# led_master.net
KiCad netlist of a schematic drawn in EAGLE
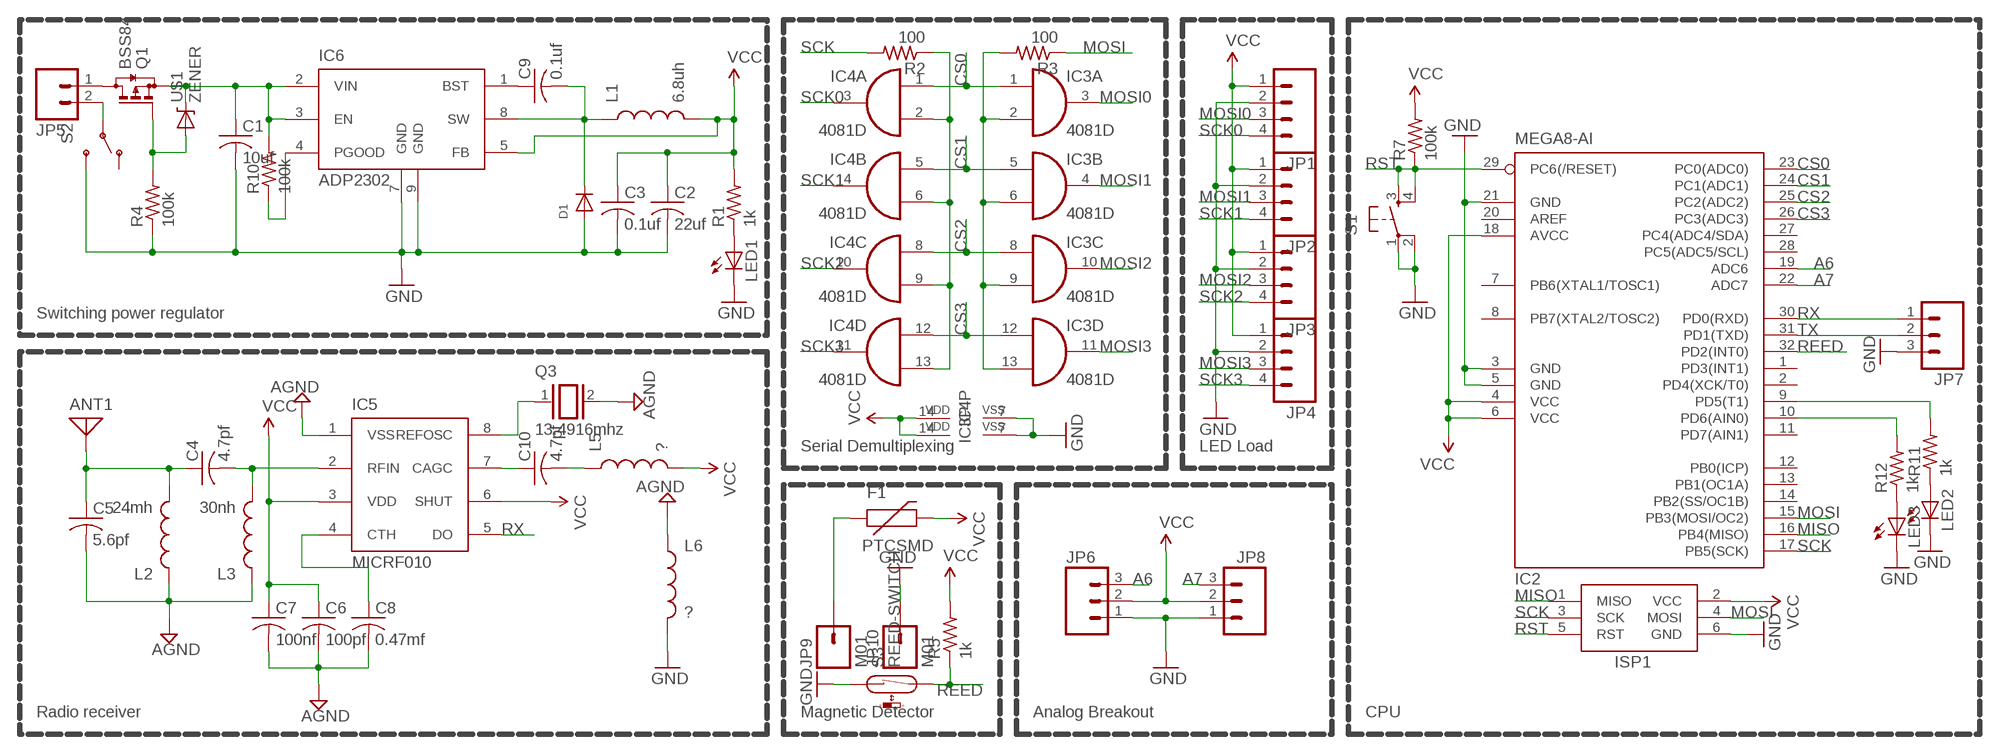
[diagram p0: schematic, sheet 1]

(export (version "E")
  (design (tool "Eeschema 10.0.6"))
  (components
    (comp (ref "ANT1")
      (value "ANTENNA")
      (footprint "eagle-import:PAD-01")
      (libsource (lib "eagle-import") (part "ANTENNA"))
    )
    (comp (ref "C1")
      (value "10uf")
      (footprint "eagle-import:C1206")
      (libsource (lib "eagle-import") (part "C-USC1206"))
    )
    (comp (ref "C2")
      (value "22uf")
      (footprint "eagle-import:C1206")
      (libsource (lib "eagle-import") (part "C-USC1206"))
    )
    (comp (ref "C3")
      (value "0.1uf")
      (footprint "eagle-import:C1206")
      (libsource (lib "eagle-import") (part "C-USC1206"))
    )
    (comp (ref "C4")
      (value "4.7pf")
      (footprint "eagle-import:C1206")
      (libsource (lib "eagle-import") (part "C-USC1206"))
    )
    (comp (ref "C5")
      (value "5.6pf")
      (footprint "eagle-import:C1206")
      (libsource (lib "eagle-import") (part "C-USC1206"))
    )
    (comp (ref "C6")
      (value "100pf")
      (footprint "eagle-import:C1206")
      (libsource (lib "eagle-import") (part "C-USC1206"))
    )
    (comp (ref "C7")
      (value "100nf")
      (footprint "eagle-import:C1206")
      (libsource (lib "eagle-import") (part "C-USC1206"))
    )
    (comp (ref "C8")
      (value "0.47mf")
      (footprint "eagle-import:C1206")
      (libsource (lib "eagle-import") (part "C-USC1206"))
    )
    (comp (ref "C9")
      (value "0.1uf")
      (footprint "eagle-import:C1206")
      (libsource (lib "eagle-import") (part "C-USC1206"))
    )
    (comp (ref "C10")
      (value "4.7pf")
      (footprint "eagle-import:C1206")
      (libsource (lib "eagle-import") (part "C-USC1206"))
    )
    (comp (ref "D1")
      (value "DIODESOD-123")
      (footprint "eagle-import:SOD-123")
      (libsource (lib "eagle-import") (part "DIODESOD-123"))
    )
    (comp (ref "F1")
      (value "PTCSMD")
      (footprint "eagle-import:PTC-1206")
      (libsource (lib "eagle-import") (part "PTCSMD"))
    )
    (comp (ref "IC2")
      (value "MEGA8-AI")
      (footprint "eagle-import:TQFP32-08")
      (fields (field (name "MPN") "ATMEGA8-16AU"))
      (libsource (lib "eagle-import") (part "MEGA8-AI"))
    )
    (comp (ref "IC3")
      (value "4081D")
      (footprint "eagle-import:SO14")
      (libsource (lib "eagle-import") (part "4081D"))
    )
    (comp (ref "IC4")
      (value "4081D")
      (footprint "eagle-import:SO14")
      (libsource (lib "eagle-import") (part "4081D"))
    )
    (comp (ref "IC5")
      (value "MICRF010")
      (footprint "eagle-import:SOIC8")
      (libsource (lib "eagle-import") (part "MICRF010"))
    )
    (comp (ref "IC6")
      (value "ADP2302")
      (footprint "eagle-import:SOIC8-PAD")
      (libsource (lib "eagle-import") (part "ADP2302"))
    )
    (comp (ref "ISP1")
      (value "AVRISP-6")
      (footprint "eagle-import:AVRISP")
      (libsource (lib "eagle-import") (part "AVRISP-6"))
    )
    (comp (ref "JP1")
      (value "M04LONGPADS")
      (footprint "eagle-import:1X04_LONGPADS")
      (libsource (lib "eagle-import") (part "M04LONGPADS"))
    )
    (comp (ref "JP2")
      (value "M04LONGPADS")
      (footprint "eagle-import:1X04_LONGPADS")
      (libsource (lib "eagle-import") (part "M04LONGPADS"))
    )
    (comp (ref "JP3")
      (value "M04LONGPADS")
      (footprint "eagle-import:1X04_LONGPADS")
      (libsource (lib "eagle-import") (part "M04LONGPADS"))
    )
    (comp (ref "JP4")
      (value "M04LONGPADS")
      (footprint "eagle-import:1X04_LONGPADS")
      (libsource (lib "eagle-import") (part "M04LONGPADS"))
    )
    (comp (ref "JP5")
      (value "M02-JST-2MM-SMT")
      (footprint "eagle-import:JST-2-SMD")
      (libsource (lib "eagle-import") (part "M02-JST-2MM-SMT"))
    )
    (comp (ref "JP6")
      (value "M03PTH")
      (footprint "eagle-import:1X03")
      (libsource (lib "eagle-import") (part "M03PTH"))
    )
    (comp (ref "JP7")
      (value "M03PTH")
      (footprint "eagle-import:1X03")
      (libsource (lib "eagle-import") (part "M03PTH"))
    )
    (comp (ref "JP8")
      (value "M03PTH")
      (footprint "eagle-import:1X03")
      (libsource (lib "eagle-import") (part "M03PTH"))
    )
    (comp (ref "JP9")
      (value "M01")
      (footprint "eagle-import:SMTSO-256-ET")
      (libsource (lib "eagle-import") (part "M01-SMTSO-256-ET"))
    )
    (comp (ref "JP10")
      (value "M01")
      (footprint "eagle-import:SMTSO-256-ET")
      (libsource (lib "eagle-import") (part "M01-SMTSO-256-ET"))
    )
    (comp (ref "L1")
      (value "6.8uh")
      (footprint "eagle-import:1210")
      (libsource (lib "eagle-import") (part "INDUCTOR1210"))
    )
    (comp (ref "L2")
      (value "24mh")
      (footprint "eagle-import:1210")
      (libsource (lib "eagle-import") (part "INDUCTOR1210"))
    )
    (comp (ref "L3")
      (value "30nh")
      (footprint "eagle-import:1210")
      (libsource (lib "eagle-import") (part "INDUCTOR1210"))
    )
    (comp (ref "L5")
      (value "?")
      (footprint "eagle-import:1210")
      (libsource (lib "eagle-import") (part "INDUCTOR1210"))
    )
    (comp (ref "L6")
      (value "?")
      (footprint "eagle-import:1210")
      (libsource (lib "eagle-import") (part "INDUCTOR1210"))
    )
    (comp (ref "LED1")
      (value "LEDSMT1206")
      (footprint "eagle-import:1206")
      (libsource (lib "eagle-import") (part "LEDSMT1206"))
    )
    (comp (ref "LED2")
      (value "LEDSMT1206")
      (footprint "eagle-import:1206")
      (libsource (lib "eagle-import") (part "LEDSMT1206"))
    )
    (comp (ref "LED3")
      (value "LEDSMT1206")
      (footprint "eagle-import:1206")
      (libsource (lib "eagle-import") (part "LEDSMT1206"))
    )
    (comp (ref "Q1")
      (value "BSS84")
      (footprint "eagle-import:SOT23")
      (libsource (lib "eagle-import") (part "BSS84"))
    )
    (comp (ref "Q3")
      (value "13.4916mhz")
      (footprint "eagle-import:QS")
      (libsource (lib "eagle-import") (part "XTAL/S"))
    )
    (comp (ref "R1")
      (value "1k")
      (footprint "eagle-import:R1206")
      (libsource (lib "eagle-import") (part "R-US_R1206"))
    )
    (comp (ref "R2")
      (value "100")
      (footprint "eagle-import:R1206")
      (libsource (lib "eagle-import") (part "R-US_R1206"))
    )
    (comp (ref "R3")
      (value "100")
      (footprint "eagle-import:R1206")
      (libsource (lib "eagle-import") (part "R-US_R1206"))
    )
    (comp (ref "R4")
      (value "100k")
      (footprint "eagle-import:R1206")
      (libsource (lib "eagle-import") (part "R-US_R1206"))
    )
    (comp (ref "R5")
      (value "1k")
      (footprint "eagle-import:R1206")
      (libsource (lib "eagle-import") (part "R-US_R1206"))
    )
    (comp (ref "R7")
      (value "100k")
      (footprint "eagle-import:R1206")
      (libsource (lib "eagle-import") (part "R-US_R1206"))
    )
    (comp (ref "R10")
      (value "100k")
      (footprint "eagle-import:R1206")
      (libsource (lib "eagle-import") (part "R-US_R1206"))
    )
    (comp (ref "R11")
      (value "1k")
      (footprint "eagle-import:R1206")
      (libsource (lib "eagle-import") (part "R-US_R1206"))
    )
    (comp (ref "R12")
      (value "1k")
      (footprint "eagle-import:R1206")
      (libsource (lib "eagle-import") (part "R-US_R1206"))
    )
    (comp (ref "S1")
      (value "TAC_SWITCHSMD")
      (footprint "eagle-import:TACTILE_SWITCH_SMD")
      (libsource (lib "eagle-import") (part "TAC_SWITCHSMD"))
    )
    (comp (ref "S2")
      (value "SWITCH-SPSTSMD2")
      (footprint "eagle-import:SWITCH-SPDT-SMD")
      (libsource (lib "eagle-import") (part "SWITCH-SPSTSMD2"))
    )
    (comp (ref "S3")
      (value "REED-SWITCH")
      (footprint "eagle-import:CT10-G1")
      (fields (field (name "MF") "COTO TECHNOLOGY") (field (name "MPN") "CT10-1530-G1"))
      (libsource (lib "eagle-import") (part "REED-SWITCH-CT10-1530-G1"))
    )
    (comp (ref "U$1")
      (value "ZENER")
      (footprint "eagle-import:SOD-323")
      (libsource (lib "eagle-import") (part "DIODE-ZENER-BZT52"))
    )
  )
  (nets
    (net (code "1") (name "/A6") (class "Default")
      (node (ref "IC2") (pin "19") (pinfunction "ADC6_19") (pintype "bidirectional"))
      (node (ref "JP6") (pin "3") (pinfunction "3_3") (pintype "passive"))
    )
    (net (code "2") (name "/A7") (class "Default")
      (node (ref "IC2") (pin "22") (pinfunction "ADC7_22") (pintype "bidirectional"))
      (node (ref "JP8") (pin "3") (pinfunction "3_3") (pintype "passive"))
    )
    (net (code "3") (name "/CS0") (class "Default")
      (node (ref "IC2") (pin "23") (pinfunction "PC0(ADC0)_23") (pintype "bidirectional"))
      (node (ref "IC3") (pin "1") (pinfunction "I0_1") (pintype "input"))
      (node (ref "IC4") (pin "1") (pinfunction "I0_1") (pintype "input"))
    )
    (net (code "4") (name "/CS1") (class "Default")
      (node (ref "IC2") (pin "24") (pinfunction "PC1(ADC1)_24") (pintype "bidirectional"))
      (node (ref "IC3") (pin "5") (pinfunction "I0_5") (pintype "input"))
      (node (ref "IC4") (pin "5") (pinfunction "I0_5") (pintype "input"))
    )
    (net (code "5") (name "/CS2") (class "Default")
      (node (ref "IC2") (pin "25") (pinfunction "PC2(ADC2)_25") (pintype "bidirectional"))
      (node (ref "IC3") (pin "8") (pinfunction "I0_8") (pintype "input"))
      (node (ref "IC4") (pin "8") (pinfunction "I0_8") (pintype "input"))
    )
    (net (code "6") (name "/CS3") (class "Default")
      (node (ref "IC2") (pin "26") (pinfunction "PC3(ADC3)_26") (pintype "bidirectional"))
      (node (ref "IC3") (pin "12") (pinfunction "I0_12") (pintype "input"))
      (node (ref "IC4") (pin "12") (pinfunction "I0_12") (pintype "input"))
    )
    (net (code "7") (name "/MISO") (class "Default")
      (node (ref "IC2") (pin "16") (pinfunction "PB4(MISO)_16") (pintype "bidirectional"))
      (node (ref "ISP1") (pin "1") (pinfunction "MISO_1") (pintype "input"))
    )
    (net (code "8") (name "/MOSI") (class "Default")
      (node (ref "IC2") (pin "15") (pinfunction "PB3(MOSI/OC2)_15") (pintype "bidirectional"))
      (node (ref "ISP1") (pin "4") (pinfunction "MOSI_4") (pintype "output"))
      (node (ref "R3") (pin "1") (pinfunction "1_1") (pintype "passive"))
    )
    (net (code "9") (name "/MOSI0") (class "Default")
      (node (ref "IC3") (pin "3") (pinfunction "O_3") (pintype "output"))
      (node (ref "JP1") (pin "3") (pinfunction "3_3") (pintype "passive"))
    )
    (net (code "10") (name "/MOSI1") (class "Default")
      (node (ref "IC3") (pin "4") (pinfunction "O_4") (pintype "output"))
      (node (ref "JP2") (pin "3") (pinfunction "3_3") (pintype "passive"))
    )
    (net (code "11") (name "/MOSI2") (class "Default")
      (node (ref "IC3") (pin "10") (pinfunction "O_10") (pintype "output"))
      (node (ref "JP3") (pin "3") (pinfunction "3_3") (pintype "passive"))
    )
    (net (code "12") (name "/MOSI3") (class "Default")
      (node (ref "IC3") (pin "11") (pinfunction "O_11") (pintype "output"))
      (node (ref "JP4") (pin "3") (pinfunction "3_3") (pintype "passive"))
    )
    (net (code "13") (name "/REED") (class "Default")
      (node (ref "IC2") (pin "32") (pinfunction "PD2(INT0)_32") (pintype "bidirectional"))
      (node (ref "R5") (pin "1") (pinfunction "1_1") (pintype "passive"))
      (node (ref "S3") (pin "2") (pinfunction "2_2") (pintype "passive"))
    )
    (net (code "14") (name "/RST") (class "Default")
      (node (ref "IC2") (pin "29") (pinfunction "PC6(/RESET)_29") (pintype "bidirectional"))
      (node (ref "ISP1") (pin "5") (pinfunction "RST_5") (pintype "output"))
      (node (ref "R7") (pin "1") (pinfunction "1_1") (pintype "passive"))
      (node (ref "S1") (pin "3") (pinfunction "3_3") (pintype "passive"))
      (node (ref "S1") (pin "4") (pinfunction "4_4") (pintype "passive"))
    )
    (net (code "15") (name "/RX") (class "Default")
      (node (ref "IC2") (pin "30") (pinfunction "PD0(RXD)_30") (pintype "bidirectional"))
      (node (ref "IC5") (pin "5") (pinfunction "DO_5") (pintype "bidirectional"))
      (node (ref "JP7") (pin "1") (pinfunction "1_1") (pintype "passive"))
    )
    (net (code "16") (name "/SCK") (class "Default")
      (node (ref "IC2") (pin "17") (pinfunction "PB5(SCK)_17") (pintype "bidirectional"))
      (node (ref "ISP1") (pin "3") (pinfunction "SCK_3") (pintype "output"))
      (node (ref "R2") (pin "2") (pinfunction "2_2") (pintype "passive"))
    )
    (net (code "17") (name "/SCK0") (class "Default")
      (node (ref "IC4") (pin "3") (pinfunction "O_3") (pintype "output"))
      (node (ref "JP1") (pin "4") (pinfunction "4_4") (pintype "passive"))
    )
    (net (code "18") (name "/SCK1") (class "Default")
      (node (ref "IC4") (pin "4") (pinfunction "O_4") (pintype "output"))
      (node (ref "JP2") (pin "4") (pinfunction "4_4") (pintype "passive"))
    )
    (net (code "19") (name "/SCK2") (class "Default")
      (node (ref "IC4") (pin "10") (pinfunction "O_10") (pintype "output"))
      (node (ref "JP3") (pin "4") (pinfunction "4_4") (pintype "passive"))
    )
    (net (code "20") (name "/SCK3") (class "Default")
      (node (ref "IC4") (pin "11") (pinfunction "O_11") (pintype "output"))
      (node (ref "JP4") (pin "4") (pinfunction "4_4") (pintype "passive"))
    )
    (net (code "21") (name "/TX") (class "Default")
      (node (ref "IC2") (pin "31") (pinfunction "PD1(TXD)_31") (pintype "bidirectional"))
      (node (ref "JP7") (pin "2") (pinfunction "2_2") (pintype "passive"))
    )
    (net (code "22") (name "AGND") (class "Default")
      (node (ref "C5") (pin "2") (pinfunction "2_2") (pintype "passive"))
      (node (ref "C6") (pin "2") (pinfunction "2_2") (pintype "passive"))
      (node (ref "C7") (pin "2") (pinfunction "2_2") (pintype "passive"))
      (node (ref "C8") (pin "2") (pinfunction "2_2") (pintype "passive"))
      (node (ref "IC5") (pin "1") (pinfunction "VSS_1") (pintype "bidirectional"))
      (node (ref "L2") (pin "1") (pinfunction "1_1") (pintype "passive"))
      (node (ref "L3") (pin "1") (pinfunction "1_1") (pintype "passive"))
      (node (ref "L6") (pin "1") (pinfunction "1_1") (pintype "passive"))
      (node (ref "Q3") (pin "2") (pinfunction "2_2") (pintype "passive"))
    )
    (net (code "23") (name "GND") (class "Default")
      (node (ref "C1") (pin "2") (pinfunction "2_2") (pintype "passive"))
      (node (ref "C2") (pin "2") (pinfunction "2_2") (pintype "passive"))
      (node (ref "C3") (pin "2") (pinfunction "2_2") (pintype "passive"))
      (node (ref "D1") (pin "A") (pinfunction "A_A") (pintype "passive"))
      (node (ref "IC2") (pin "21") (pinfunction "GND_21") (pintype "power_in"))
      (node (ref "IC2") (pin "3") (pinfunction "GND_3") (pintype "power_in"))
      (node (ref "IC2") (pin "5") (pinfunction "GND_5") (pintype "power_in"))
      (node (ref "IC3") (pin "7") (pinfunction "VSS_7") (pintype "power_in"))
      (node (ref "IC4") (pin "7") (pinfunction "VSS_7") (pintype "power_in"))
      (node (ref "IC6") (pin "7") (pinfunction "GND_7") (pintype "bidirectional"))
      (node (ref "IC6") (pin "9") (pinfunction "GND_9") (pintype "bidirectional"))
      (node (ref "ISP1") (pin "6") (pinfunction "GND_6") (pintype "power_in"))
      (node (ref "JP1") (pin "2") (pinfunction "2_2") (pintype "passive"))
      (node (ref "JP10") (pin "P$1") (pinfunction "1_P$1") (pintype "passive"))
      (node (ref "JP2") (pin "2") (pinfunction "2_2") (pintype "passive"))
      (node (ref "JP3") (pin "2") (pinfunction "2_2") (pintype "passive"))
      (node (ref "JP4") (pin "2") (pinfunction "2_2") (pintype "passive"))
      (node (ref "JP6") (pin "1") (pinfunction "1_1") (pintype "passive"))
      (node (ref "JP7") (pin "3") (pinfunction "3_3") (pintype "passive"))
      (node (ref "JP8") (pin "1") (pinfunction "1_1") (pintype "passive"))
      (node (ref "L6") (pin "2") (pinfunction "2_2") (pintype "passive"))
      (node (ref "LED1") (pin "C") (pinfunction "C_C") (pintype "passive"))
      (node (ref "LED2") (pin "C") (pinfunction "C_C") (pintype "passive"))
      (node (ref "LED3") (pin "C") (pinfunction "C_C") (pintype "passive"))
      (node (ref "R4") (pin "1") (pinfunction "1_1") (pintype "passive"))
      (node (ref "S1") (pin "1") (pinfunction "1_1") (pintype "passive"))
      (node (ref "S1") (pin "2") (pinfunction "2_2") (pintype "passive"))
      (node (ref "S2") (pin "3") (pinfunction "S_3") (pintype "passive"))
      (node (ref "S3") (pin "1") (pinfunction "1_1") (pintype "passive"))
    )
    (net (code "24") (name "Net-(ANT1-Pad1)") (class "Default")
      (node (ref "ANT1") (pin "1") (pinfunction "1_1") (pintype "output"))
      (node (ref "C4") (pin "1") (pinfunction "1_1") (pintype "passive"))
      (node (ref "C5") (pin "1") (pinfunction "1_1") (pintype "passive"))
      (node (ref "L2") (pin "2") (pinfunction "2_2") (pintype "passive"))
    )
    (net (code "25") (name "Net-(C10-Pad2)") (class "Default")
      (node (ref "C10") (pin "2") (pinfunction "2_2") (pintype "passive"))
      (node (ref "L5") (pin "1") (pinfunction "1_1") (pintype "passive"))
    )
    (net (code "26") (name "Net-(IC2-PD5(T1))") (class "Default")
      (node (ref "IC2") (pin "9") (pinfunction "PD5(T1)_9") (pintype "bidirectional"))
      (node (ref "R11") (pin "2") (pinfunction "2_2") (pintype "passive"))
    )
    (net (code "27") (name "Net-(IC2-PD6(AIN0))") (class "Default")
      (node (ref "IC2") (pin "10") (pinfunction "PD6(AIN0)_10") (pintype "bidirectional"))
      (node (ref "R12") (pin "2") (pinfunction "2_2") (pintype "passive"))
    )
    (net (code "28") (name "Net-(IC3A-I1)") (class "Default")
      (node (ref "IC3") (pin "13") (pinfunction "I1_13") (pintype "input"))
      (node (ref "IC3") (pin "2") (pinfunction "I1_2") (pintype "input"))
      (node (ref "IC3") (pin "6") (pinfunction "I1_6") (pintype "input"))
      (node (ref "IC3") (pin "9") (pinfunction "I1_9") (pintype "input"))
      (node (ref "R3") (pin "2") (pinfunction "2_2") (pintype "passive"))
    )
    (net (code "29") (name "Net-(IC4A-I1)") (class "Default")
      (node (ref "IC4") (pin "13") (pinfunction "I1_13") (pintype "input"))
      (node (ref "IC4") (pin "2") (pinfunction "I1_2") (pintype "input"))
      (node (ref "IC4") (pin "6") (pinfunction "I1_6") (pintype "input"))
      (node (ref "IC4") (pin "9") (pinfunction "I1_9") (pintype "input"))
      (node (ref "R2") (pin "1") (pinfunction "1_1") (pintype "passive"))
    )
    (net (code "30") (name "Net-(IC5-CAGC)") (class "Default")
      (node (ref "C10") (pin "1") (pinfunction "1_1") (pintype "passive"))
      (node (ref "IC5") (pin "7") (pinfunction "CAGC_7") (pintype "bidirectional"))
    )
    (net (code "31") (name "Net-(IC5-CTH)") (class "Default")
      (node (ref "C8") (pin "1") (pinfunction "1_1") (pintype "passive"))
      (node (ref "IC5") (pin "4") (pinfunction "CTH_4") (pintype "bidirectional"))
    )
    (net (code "32") (name "Net-(IC5-REFOSC)") (class "Default")
      (node (ref "IC5") (pin "8") (pinfunction "REFOSC_8") (pintype "bidirectional"))
      (node (ref "Q3") (pin "1") (pinfunction "1_1") (pintype "passive"))
    )
    (net (code "33") (name "Net-(IC5-RFIN)") (class "Default")
      (node (ref "C4") (pin "2") (pinfunction "2_2") (pintype "passive"))
      (node (ref "IC5") (pin "2") (pinfunction "RFIN_2") (pintype "bidirectional"))
      (node (ref "L3") (pin "2") (pinfunction "2_2") (pintype "passive"))
    )
    (net (code "34") (name "Net-(IC6-BST)") (class "Default")
      (node (ref "C9") (pin "1") (pinfunction "1_1") (pintype "passive"))
      (node (ref "IC6") (pin "1") (pinfunction "BST_1") (pintype "bidirectional"))
    )
    (net (code "35") (name "Net-(IC6-EN)") (class "Default")
      (node (ref "C1") (pin "1") (pinfunction "1_1") (pintype "passive"))
      (node (ref "IC6") (pin "2") (pinfunction "VIN_2") (pintype "bidirectional"))
      (node (ref "IC6") (pin "3") (pinfunction "EN_3") (pintype "bidirectional"))
      (node (ref "Q1") (pin "2") (pinfunction "S_2") (pintype "passive"))
      (node (ref "R10") (pin "2") (pinfunction "2_2") (pintype "passive"))
      (node (ref "U$1") (pin "1") (pinfunction "C_1") (pintype "passive"))
    )
    (net (code "36") (name "Net-(IC6-PGOOD)") (class "Default")
      (node (ref "IC6") (pin "4") (pinfunction "PGOOD_4") (pintype "bidirectional"))
      (node (ref "R10") (pin "1") (pinfunction "1_1") (pintype "passive"))
    )
    (net (code "37") (name "Net-(IC6-SW)") (class "Default")
      (node (ref "C9") (pin "2") (pinfunction "2_2") (pintype "passive"))
      (node (ref "D1") (pin "C") (pinfunction "C_C") (pintype "passive"))
      (node (ref "IC6") (pin "8") (pinfunction "SW_8") (pintype "bidirectional"))
      (node (ref "L1") (pin "1") (pinfunction "1_1") (pintype "passive"))
    )
    (net (code "38") (name "Net-(JP9-1)") (class "Default")
      (node (ref "F1") (pin "1") (pinfunction "1_1") (pintype "bidirectional"))
      (node (ref "JP9") (pin "P$1") (pinfunction "1_P$1") (pintype "passive"))
    )
    (net (code "39") (name "Net-(LED1-PadA)") (class "Default")
      (node (ref "LED1") (pin "A") (pinfunction "A_A") (pintype "passive"))
      (node (ref "R1") (pin "1") (pinfunction "1_1") (pintype "passive"))
    )
    (net (code "40") (name "Net-(LED2-PadA)") (class "Default")
      (node (ref "LED2") (pin "A") (pinfunction "A_A") (pintype "passive"))
      (node (ref "R11") (pin "1") (pinfunction "1_1") (pintype "passive"))
    )
    (net (code "41") (name "Net-(LED3-PadA)") (class "Default")
      (node (ref "LED3") (pin "A") (pinfunction "A_A") (pintype "passive"))
      (node (ref "R12") (pin "1") (pinfunction "1_1") (pintype "passive"))
    )
    (net (code "42") (name "Net-(Q1-D)") (class "Default")
      (node (ref "JP5") (pin "1") (pinfunction "1_1") (pintype "passive"))
      (node (ref "Q1") (pin "3") (pinfunction "D_3") (pintype "passive"))
    )
    (net (code "43") (name "Net-(Q1-G)") (class "Default")
      (node (ref "Q1") (pin "1") (pinfunction "G_1") (pintype "passive"))
      (node (ref "R4") (pin "2") (pinfunction "2_2") (pintype "passive"))
      (node (ref "U$1") (pin "2") (pinfunction "A_2") (pintype "passive"))
    )
    (net (code "44") (name "Net-(S2-P)") (class "Default")
      (node (ref "JP5") (pin "2") (pinfunction "2_2") (pintype "passive"))
      (node (ref "S2") (pin "2") (pinfunction "P_2") (pintype "passive"))
    )
    (net (code "45") (name "VCC") (class "Default")
      (node (ref "C2") (pin "1") (pinfunction "1_1") (pintype "passive"))
      (node (ref "C3") (pin "1") (pinfunction "1_1") (pintype "passive"))
      (node (ref "C6") (pin "1") (pinfunction "1_1") (pintype "passive"))
      (node (ref "C7") (pin "1") (pinfunction "1_1") (pintype "passive"))
      (node (ref "F1") (pin "2") (pinfunction "2_2") (pintype "bidirectional"))
      (node (ref "IC2") (pin "18") (pinfunction "AVCC_18") (pintype "power_in"))
      (node (ref "IC2") (pin "4") (pinfunction "VCC_4") (pintype "power_in"))
      (node (ref "IC2") (pin "6") (pinfunction "VCC_6") (pintype "power_in"))
      (node (ref "IC3") (pin "14") (pinfunction "VDD_14") (pintype "power_in"))
      (node (ref "IC4") (pin "14") (pinfunction "VDD_14") (pintype "power_in"))
      (node (ref "IC5") (pin "3") (pinfunction "VDD_3") (pintype "bidirectional"))
      (node (ref "IC5") (pin "6") (pinfunction "SHUT_6") (pintype "bidirectional"))
      (node (ref "IC6") (pin "5") (pinfunction "FB_5") (pintype "bidirectional"))
      (node (ref "ISP1") (pin "2") (pinfunction "VCC_2") (pintype "power_in"))
      (node (ref "JP1") (pin "1") (pinfunction "1_1") (pintype "passive"))
      (node (ref "JP2") (pin "1") (pinfunction "1_1") (pintype "passive"))
      (node (ref "JP3") (pin "1") (pinfunction "1_1") (pintype "passive"))
      (node (ref "JP4") (pin "1") (pinfunction "1_1") (pintype "passive"))
      (node (ref "JP6") (pin "2") (pinfunction "2_2") (pintype "passive"))
      (node (ref "JP8") (pin "2") (pinfunction "2_2") (pintype "passive"))
      (node (ref "L1") (pin "2") (pinfunction "2_2") (pintype "passive"))
      (node (ref "L5") (pin "2") (pinfunction "2_2") (pintype "passive"))
      (node (ref "R1") (pin "2") (pinfunction "2_2") (pintype "passive"))
      (node (ref "R5") (pin "2") (pinfunction "2_2") (pintype "passive"))
      (node (ref "R7") (pin "2") (pinfunction "2_2") (pintype "passive"))
    )
    (net (code "46") (name "unconnected-(IC2-AREF-Pad20)") (class "Default")
      (node (ref "IC2") (pin "20") (pinfunction "AREF_20") (pintype "passive"))
    )
    (net (code "47") (name "unconnected-(IC2-PB0(ICP)-Pad12)") (class "Default")
      (node (ref "IC2") (pin "12") (pinfunction "PB0(ICP)_12") (pintype "bidirectional"))
    )
    (net (code "48") (name "unconnected-(IC2-PB1(OC1A)-Pad13)") (class "Default")
      (node (ref "IC2") (pin "13") (pinfunction "PB1(OC1A)_13") (pintype "bidirectional"))
    )
    (net (code "49") (name "unconnected-(IC2-PB2(SS{slash}OC1B)-Pad14)") (class "Default")
      (node (ref "IC2") (pin "14") (pinfunction "PB2(SS/OC1B)_14") (pintype "bidirectional"))
    )
    (net (code "50") (name "unconnected-(IC2-PB6(XTAL1{slash}TOSC1)-Pad7)") (class "Default")
      (node (ref "IC2") (pin "7") (pinfunction "PB6(XTAL1/TOSC1)_7") (pintype "bidirectional"))
    )
    (net (code "51") (name "unconnected-(IC2-PB7(XTAL2{slash}TOSC2)-Pad8)") (class "Default")
      (node (ref "IC2") (pin "8") (pinfunction "PB7(XTAL2/TOSC2)_8") (pintype "bidirectional"))
    )
    (net (code "52") (name "unconnected-(IC2-PC4(ADC4{slash}SDA)-Pad27)") (class "Default")
      (node (ref "IC2") (pin "27") (pinfunction "PC4(ADC4/SDA)_27") (pintype "bidirectional"))
    )
    (net (code "53") (name "unconnected-(IC2-PC5(ADC5{slash}SCL)-Pad28)") (class "Default")
      (node (ref "IC2") (pin "28") (pinfunction "PC5(ADC5/SCL)_28") (pintype "bidirectional"))
    )
    (net (code "54") (name "unconnected-(IC2-PD3(INT1)-Pad1)") (class "Default")
      (node (ref "IC2") (pin "1") (pinfunction "PD3(INT1)_1") (pintype "bidirectional"))
    )
    (net (code "55") (name "unconnected-(IC2-PD4(XCK{slash}T0)-Pad2)") (class "Default")
      (node (ref "IC2") (pin "2") (pinfunction "PD4(XCK/T0)_2") (pintype "bidirectional"))
    )
    (net (code "56") (name "unconnected-(IC2-PD7(AIN1)-Pad11)") (class "Default")
      (node (ref "IC2") (pin "11") (pinfunction "PD7(AIN1)_11") (pintype "bidirectional"))
    )
    (net (code "57") (name "unconnected-(S2-O-Pad1)") (class "Default")
      (node (ref "S2") (pin "1") (pinfunction "O_1") (pintype "passive"))
    )
  )
)
